# Power_Board_DRV8323.net
KiCad netlist of a schematic drawn in Altium Designer
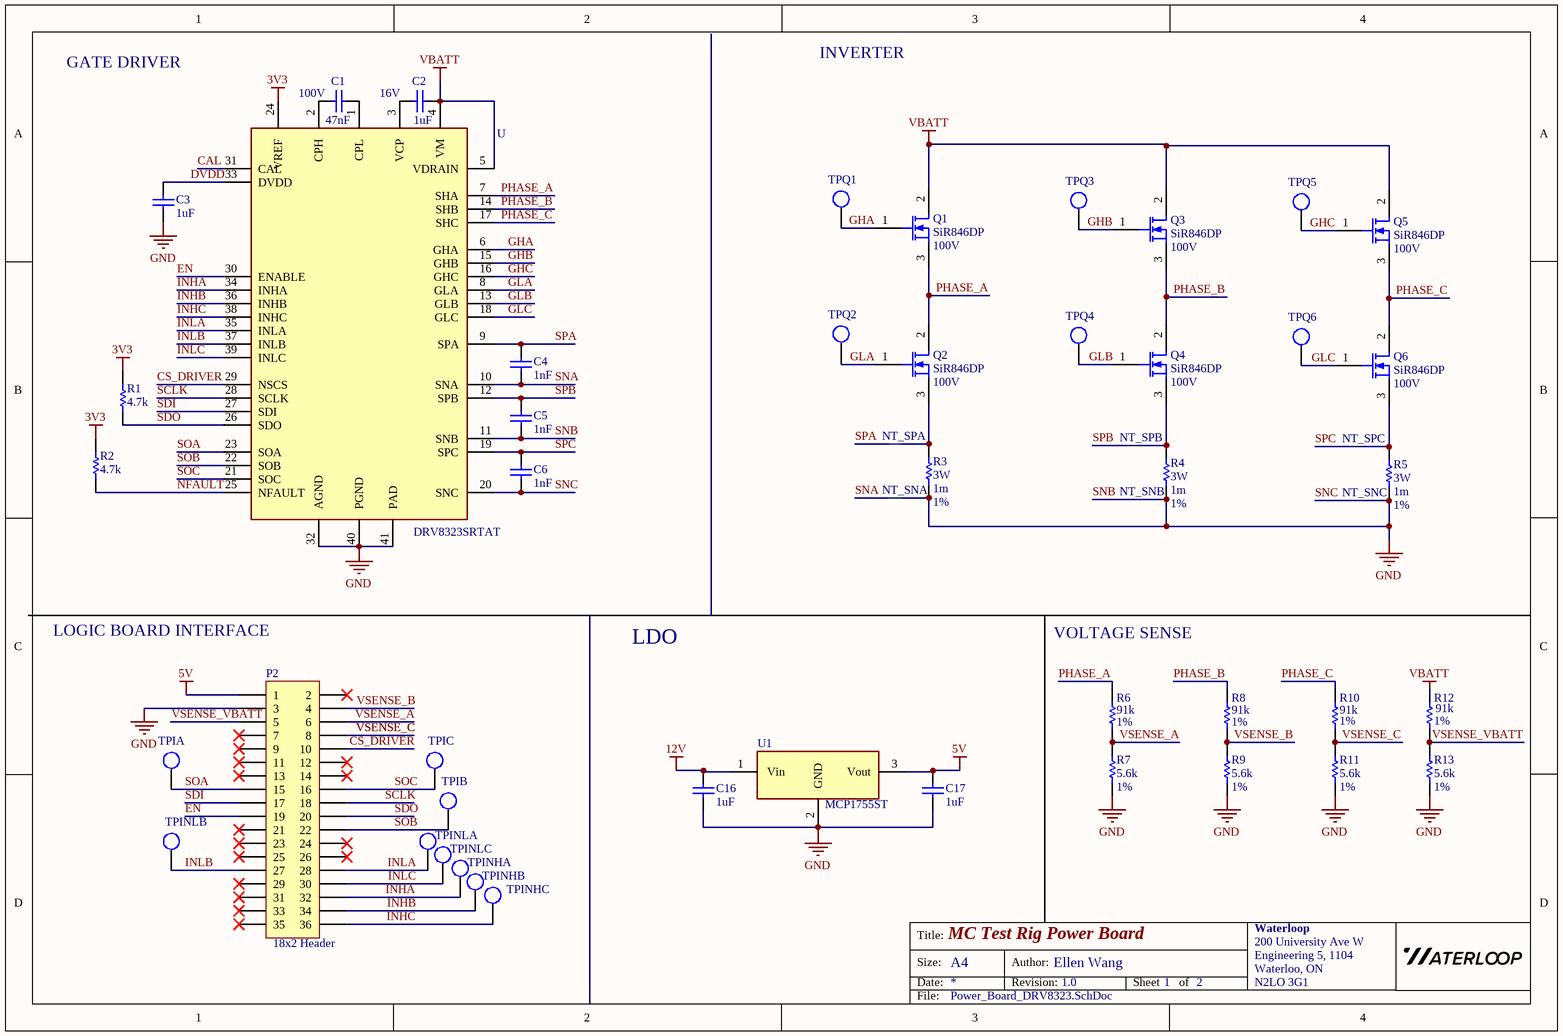
[diagram p0: Power_Board_DRV8323.SchDoc]

(export (version "E")
  (design (tool "Eeschema 10.0.6"))
  (components
    (comp (ref "C1")
      (value "47nF")
      (footprint "0805 - Capacitor")
      (description "Nonpolarized Capacitor")
      (fields
        (field (name "MANUFACTURER") "YAGEO")
        (field (name "RATING") "100V")
        (field (name "MANUFACTURER PART NUMBER") "CC0805KKX7R0BB473")
      )
      (libsource (lib "General") (part "Capacitor - Nonpolarized"))
    )
    (comp (ref "C2")
      (value "1uF")
      (footprint "0805 - Capacitor")
      (description "Nonpolarized Capacitor")
      (fields
        (field (name "MANUFACTURER") "YAGEO")
        (field (name "RATING") "16V")
        (field (name "MANUFACTURER PART NUMBER") "CC0805KKX7R7BB105")
      )
      (libsource (lib "General") (part "Capacitor - Nonpolarized"))
    )
    (comp (ref "C3")
      (value "1uF")
      (footprint "0805 - Capacitor")
      (description "Nonpolarized Capacitor")
      (fields
        (field (name "MANUFACTURER") "YAGEO")
        (field (name "MANUFACTURER PART NUMBER") "CC0805KKX7R7BB105")
      )
      (libsource (lib "General") (part "Capacitor - Nonpolarized"))
    )
    (comp (ref "C4")
      (value "1nF")
      (footprint "0805 - Capacitor")
      (description "Nonpolarized Capacitor")
      (fields
        (field (name "MANUFACTURER") "YAGEO")
        (field (name "MANUFACTURER PART NUMBER") "CC0805KRX7R0BB102")
      )
      (libsource (lib "General") (part "Capacitor - Nonpolarized"))
    )
    (comp (ref "C5")
      (value "1nF")
      (footprint "0805 - Capacitor")
      (description "Nonpolarized Capacitor")
      (fields
        (field (name "MANUFACTURER") "YAGEO")
        (field (name "MANUFACTURER PART NUMBER") "CC0805KRX7R0BB102")
      )
      (libsource (lib "General") (part "Capacitor - Nonpolarized"))
    )
    (comp (ref "C6")
      (value "1nF")
      (footprint "0805 - Capacitor")
      (description "Nonpolarized Capacitor")
      (fields
        (field (name "MANUFACTURER") "YAGEO")
        (field (name "MANUFACTURER PART NUMBER") "CC0805KRX7R0BB102")
      )
      (libsource (lib "General") (part "Capacitor - Nonpolarized"))
    )
    (comp (ref "C16")
      (value "1uF")
      (footprint "0805 - Capacitor")
      (description "Nonpolarized Capacitor")
      (fields (field (name "Comment") "Capacitor - Nonpolarized"))
      (libsource (lib "General") (part "Capacitor - Nonpolarized"))
    )
    (comp (ref "C17")
      (value "1uF")
      (footprint "0805 - Capacitor")
      (description "Nonpolarized Capacitor")
      (fields (field (name "Comment") "Capacitor - Nonpolarized"))
      (libsource (lib "General") (part "Capacitor - Nonpolarized"))
    )
    (comp (ref "NT_SNA") (value "NetTie") (footprint "Net Tie") (libsource (lib "General") (part "Net Tie")))
    (comp (ref "NT_SNB") (value "NetTie") (footprint "Net Tie") (libsource (lib "General") (part "Net Tie")))
    (comp (ref "NT_SNC") (value "NetTie") (footprint "Net Tie") (libsource (lib "General") (part "Net Tie")))
    (comp (ref "NT_SPA") (value "NetTie") (footprint "Net Tie") (libsource (lib "General") (part "Net Tie")))
    (comp (ref "NT_SPB") (value "NetTie") (footprint "Net Tie") (libsource (lib "General") (part "Net Tie")))
    (comp (ref "NT_SPC") (value "NetTie") (footprint "Net Tie") (libsource (lib "General") (part "Net Tie")))
    (comp (ref "P2")
      (value "Header 18X2")
      (footprint "HDR2X18")
      (description "Header, 18-Pin, Dual row")
      (fields (field (name "PUBLISHER") "Altium Limited"))
      (libsource (lib "Miscellaneous Connectors") (part "Header 18X2"))
    )
    (comp (ref "Q1")
      (value "MOSFET-N")
      (footprint "PowerPAK® SO-8")
      (description "N-Channel MOSFET")
      (fields (field (name "SUPPLIER PART NUMBER") "SiR846DP") (field (name "RATING") "100V"))
      (libsource (lib "General") (part "MOSFET-N"))
    )
    (comp (ref "Q2")
      (value "MOSFET-N")
      (footprint "PowerPAK® SO-8")
      (description "N-Channel MOSFET")
      (fields (field (name "SUPPLIER PART NUMBER") "SiR846DP") (field (name "RATING") "100V"))
      (libsource (lib "General") (part "MOSFET-N"))
    )
    (comp (ref "Q3")
      (value "MOSFET-N")
      (footprint "PowerPAK® SO-8")
      (description "N-Channel MOSFET")
      (fields (field (name "SUPPLIER PART NUMBER") "SiR846DP") (field (name "RATING") "100V"))
      (libsource (lib "General") (part "MOSFET-N"))
    )
    (comp (ref "Q4")
      (value "MOSFET-N")
      (footprint "PowerPAK® SO-8")
      (description "N-Channel MOSFET")
      (fields (field (name "SUPPLIER PART NUMBER") "SiR846DP") (field (name "RATING") "100V"))
      (libsource (lib "General") (part "MOSFET-N"))
    )
    (comp (ref "Q5")
      (value "MOSFET-N")
      (footprint "PowerPAK® SO-8")
      (description "N-Channel MOSFET")
      (fields (field (name "SUPPLIER PART NUMBER") "SiR846DP") (field (name "RATING") "100V"))
      (libsource (lib "General") (part "MOSFET-N"))
    )
    (comp (ref "Q6")
      (value "MOSFET-N")
      (footprint "PowerPAK® SO-8")
      (description "N-Channel MOSFET")
      (fields (field (name "SUPPLIER PART NUMBER") "SiR846DP") (field (name "RATING") "100V"))
      (libsource (lib "General") (part "MOSFET-N"))
    )
    (comp (ref "R1")
      (value "4.7k")
      (footprint "0603 - Resistor")
      (description "Resistor")
      (fields
        (field (name "MANUFACTURER PART NUMBER") "RC0603FR-074K7L")
        (field (name "MANUFACTURER") "YAGEO")
      )
      (libsource (lib "General") (part "Resistor"))
    )
    (comp (ref "R2")
      (value "4.7k")
      (footprint "0603 - Resistor")
      (description "Resistor")
      (fields
        (field (name "MANUFACTURER PART NUMBER") "RC0603FR-074K7L")
        (field (name "MANUFACTURER") "YAGEO")
      )
      (libsource (lib "General") (part "Resistor"))
    )
    (comp (ref "R3")
      (value "1m")
      (footprint "2512 - RESISTOR")
      (description "Resistor")
      (fields
        (field (name "RATING") "3W")
        (field (name "MANUFACTURER PART NUMBER") "CSR2512C0R001F")
        (field (name "MANUFACTURER") "Riedon")
        (field (name "TOLERANCE") "1%")
      )
      (libsource (lib "General") (part "Resistor"))
    )
    (comp (ref "R4")
      (value "1m")
      (footprint "2512 - RESISTOR")
      (description "Resistor")
      (fields
        (field (name "RATING") "3W")
        (field (name "MANUFACTURER PART NUMBER") "CSR2512C0R001F")
        (field (name "MANUFACTURER") "Riedon")
        (field (name "TOLERANCE") "1%")
      )
      (libsource (lib "General") (part "Resistor"))
    )
    (comp (ref "R5")
      (value "1m")
      (footprint "2512 - RESISTOR")
      (description "Resistor")
      (fields
        (field (name "RATING") "3W")
        (field (name "MANUFACTURER PART NUMBER") "CSR2512C0R001F")
        (field (name "MANUFACTURER") "Riedon")
        (field (name "TOLERANCE") "1%")
      )
      (libsource (lib "General") (part "Resistor"))
    )
    (comp (ref "R6")
      (value "91k")
      (footprint "0603 - Resistor")
      (description "Resistor")
      (fields
        (field (name "MANUFACTURER PART NUMBER") "RC0603FR-0791KL")
        (field (name "MANUFACTURER") "YAGEO")
        (field (name "TOLERANCE") "1%")
      )
      (libsource (lib "General") (part "Resistor"))
    )
    (comp (ref "R7")
      (value "5.6k")
      (footprint "0603 - Resistor")
      (description "Resistor")
      (fields
        (field (name "MANUFACTURER PART NUMBER") "RC0603FR-075K6L")
        (field (name "MANUFACTURER") "YAGEO")
        (field (name "TOLERANCE") "1%")
      )
      (libsource (lib "General") (part "Resistor"))
    )
    (comp (ref "R8")
      (value "91k")
      (footprint "0603 - Resistor")
      (description "Resistor")
      (fields
        (field (name "MANUFACTURER PART NUMBER") "RC0603FR-0791KL")
        (field (name "MANUFACTURER") "YAGEO")
        (field (name "TOLERANCE") "1%")
      )
      (libsource (lib "General") (part "Resistor"))
    )
    (comp (ref "R9")
      (value "5.6k")
      (footprint "0603 - Resistor")
      (description "Resistor")
      (fields
        (field (name "MANUFACTURER PART NUMBER") "RC0603FR-075K6L")
        (field (name "MANUFACTURER") "YAGEO")
        (field (name "TOLERANCE") "1%")
      )
      (libsource (lib "General") (part "Resistor"))
    )
    (comp (ref "R10")
      (value "91k")
      (footprint "0603 - Resistor")
      (description "Resistor")
      (fields
        (field (name "MANUFACTURER PART NUMBER") "RC0603FR-0791KL")
        (field (name "MANUFACTURER") "YAGEO")
        (field (name "TOLERANCE") "1%")
      )
      (libsource (lib "General") (part "Resistor"))
    )
    (comp (ref "R11")
      (value "5.6k")
      (footprint "0603 - Resistor")
      (description "Resistor")
      (fields
        (field (name "MANUFACTURER PART NUMBER") "RC0603FR-075K6L")
        (field (name "MANUFACTURER") "YAGEO")
        (field (name "TOLERANCE") "1%")
      )
      (libsource (lib "General") (part "Resistor"))
    )
    (comp (ref "R12")
      (value "91k")
      (footprint "0603 - Resistor")
      (description "Resistor")
      (fields
        (field (name "MANUFACTURER PART NUMBER") "RC0603FR-0791KL")
        (field (name "MANUFACTURER") "YAGEO")
        (field (name "TOLERANCE") "1%")
      )
      (libsource (lib "General") (part "Resistor"))
    )
    (comp (ref "R13")
      (value "5.6k")
      (footprint "0603 - Resistor")
      (description "Resistor")
      (fields
        (field (name "MANUFACTURER PART NUMBER") "RC0603FR-075K6L")
        (field (name "MANUFACTURER") "YAGEO")
        (field (name "TOLERANCE") "1%")
      )
      (libsource (lib "General") (part "Resistor"))
    )
    (comp (ref "TPIA")
      (value "Test Point")
      (footprint "Test Point")
      (libsource (lib "General") (part "Test Point"))
    )
    (comp (ref "TPIB")
      (value "Test Point")
      (footprint "Test Point")
      (libsource (lib "General") (part "Test Point"))
    )
    (comp (ref "TPIC")
      (value "Test Point")
      (footprint "Test Point")
      (libsource (lib "General") (part "Test Point"))
    )
    (comp (ref "TPINHA")
      (value "Test Point")
      (footprint "Test Point")
      (libsource (lib "General") (part "Test Point"))
    )
    (comp (ref "TPINHB")
      (value "Test Point")
      (footprint "Test Point")
      (libsource (lib "General") (part "Test Point"))
    )
    (comp (ref "TPINHC")
      (value "Test Point")
      (footprint "Test Point")
      (libsource (lib "General") (part "Test Point"))
    )
    (comp (ref "TPINLA")
      (value "Test Point")
      (footprint "Test Point")
      (libsource (lib "General") (part "Test Point"))
    )
    (comp (ref "TPINLB")
      (value "Test Point")
      (footprint "Test Point")
      (libsource (lib "General") (part "Test Point"))
    )
    (comp (ref "TPINLC")
      (value "Test Point")
      (footprint "Test Point")
      (libsource (lib "General") (part "Test Point"))
    )
    (comp (ref "TPQ1")
      (value "Test Point")
      (footprint "Test Point")
      (libsource (lib "General") (part "Test Point"))
    )
    (comp (ref "TPQ2")
      (value "Test Point")
      (footprint "Test Point")
      (libsource (lib "General") (part "Test Point"))
    )
    (comp (ref "TPQ3")
      (value "Test Point")
      (footprint "Test Point")
      (libsource (lib "General") (part "Test Point"))
    )
    (comp (ref "TPQ4")
      (value "Test Point")
      (footprint "Test Point")
      (libsource (lib "General") (part "Test Point"))
    )
    (comp (ref "TPQ5")
      (value "Test Point")
      (footprint "Test Point")
      (libsource (lib "General") (part "Test Point"))
    )
    (comp (ref "TPQ6")
      (value "Test Point")
      (footprint "Test Point")
      (libsource (lib "General") (part "Test Point"))
    )
    (comp (ref "U")
      (value "DRV8323SRTAT")
      (footprint "DRV8323SRTAT")
      (description "Multiphase Motor Driver Power MOSFET SPI")
      (fields (field (name "MANUFACTURER") "Texas Instruments"))
      (libsource (lib "MC") (part "DRV8323SRTAT"))
    )
    (comp (ref "U1")
      (value "MCP1755ST")
      (footprint "MCP1755ST")
      (libsource (lib "GeneralComponents") (part "MCP1755ST"))
    )
  )
  (nets
    (net (code "1") (name "/CAL") (class "Default")
      (node (ref "U") (pin "31") (pinfunction "CAL_31") (pintype "passive"))
    )
    (net (code "2") (name "/CS_DRIVER") (class "Default")
      (node (ref "P2") (pin "10") (pinfunction "10_10") (pintype "passive"))
      (node (ref "U") (pin "29") (pinfunction "NSCS_29") (pintype "passive"))
    )
    (net (code "3") (name "/DVDD") (class "Default")
      (node (ref "C3") (pin "2") (pinfunction "2_2") (pintype "passive"))
      (node (ref "U") (pin "33") (pinfunction "DVDD_33") (pintype "power_in"))
    )
    (net (code "4") (name "/EN") (class "Default")
      (node (ref "P2") (pin "19") (pinfunction "19_19") (pintype "passive"))
      (node (ref "U") (pin "30") (pinfunction "ENABLE_30") (pintype "passive"))
    )
    (net (code "5") (name "/GHA") (class "Default")
      (node (ref "Q1") (pin "1") (pinfunction "G_1") (pintype "passive"))
      (node (ref "TPQ1") (pin "1") (pinfunction "0_1") (pintype "passive"))
      (node (ref "U") (pin "6") (pinfunction "GHA_6") (pintype "passive"))
    )
    (net (code "6") (name "/GHB") (class "Default")
      (node (ref "Q3") (pin "1") (pinfunction "G_1") (pintype "passive"))
      (node (ref "TPQ3") (pin "1") (pinfunction "0_1") (pintype "passive"))
      (node (ref "U") (pin "15") (pinfunction "GHB_15") (pintype "passive"))
    )
    (net (code "7") (name "/GHC") (class "Default")
      (node (ref "Q5") (pin "1") (pinfunction "G_1") (pintype "passive"))
      (node (ref "TPQ5") (pin "1") (pinfunction "0_1") (pintype "passive"))
      (node (ref "U") (pin "16") (pinfunction "GHC_16") (pintype "passive"))
    )
    (net (code "8") (name "/GLA") (class "Default")
      (node (ref "Q2") (pin "1") (pinfunction "G_1") (pintype "passive"))
      (node (ref "TPQ2") (pin "1") (pinfunction "0_1") (pintype "passive"))
      (node (ref "U") (pin "8") (pinfunction "GLA_8") (pintype "passive"))
    )
    (net (code "9") (name "/GLB") (class "Default")
      (node (ref "Q4") (pin "1") (pinfunction "G_1") (pintype "passive"))
      (node (ref "TPQ4") (pin "1") (pinfunction "0_1") (pintype "passive"))
      (node (ref "U") (pin "13") (pinfunction "GLB_13") (pintype "passive"))
    )
    (net (code "10") (name "/GLC") (class "Default")
      (node (ref "Q6") (pin "1") (pinfunction "G_1") (pintype "passive"))
      (node (ref "TPQ6") (pin "1") (pinfunction "0_1") (pintype "passive"))
      (node (ref "U") (pin "18") (pinfunction "GLC_18") (pintype "passive"))
    )
    (net (code "11") (name "/INHA") (class "Default")
      (node (ref "P2") (pin "32") (pinfunction "32_32") (pintype "passive"))
      (node (ref "TPINHA") (pin "1") (pinfunction "0_1") (pintype "passive"))
      (node (ref "U") (pin "34") (pinfunction "INHA_34") (pintype "passive"))
    )
    (net (code "12") (name "/INHB") (class "Default")
      (node (ref "P2") (pin "34") (pinfunction "34_34") (pintype "passive"))
      (node (ref "TPINHB") (pin "1") (pinfunction "0_1") (pintype "passive"))
      (node (ref "U") (pin "36") (pinfunction "INHB_36") (pintype "passive"))
    )
    (net (code "13") (name "/INHC") (class "Default")
      (node (ref "P2") (pin "36") (pinfunction "36_36") (pintype "passive"))
      (node (ref "TPINHC") (pin "1") (pinfunction "0_1") (pintype "passive"))
      (node (ref "U") (pin "38") (pinfunction "INHC_38") (pintype "passive"))
    )
    (net (code "14") (name "/INLA") (class "Default")
      (node (ref "P2") (pin "28") (pinfunction "28_28") (pintype "passive"))
      (node (ref "TPINLA") (pin "1") (pinfunction "0_1") (pintype "passive"))
      (node (ref "U") (pin "35") (pinfunction "INLA_35") (pintype "passive"))
    )
    (net (code "15") (name "/INLB") (class "Default")
      (node (ref "P2") (pin "27") (pinfunction "27_27") (pintype "passive"))
      (node (ref "TPINLB") (pin "1") (pinfunction "0_1") (pintype "passive"))
      (node (ref "U") (pin "37") (pinfunction "INLB_37") (pintype "passive"))
    )
    (net (code "16") (name "/INLC") (class "Default")
      (node (ref "P2") (pin "30") (pinfunction "30_30") (pintype "passive"))
      (node (ref "TPINLC") (pin "1") (pinfunction "0_1") (pintype "passive"))
      (node (ref "U") (pin "39") (pinfunction "INLC_39") (pintype "passive"))
    )
    (net (code "17") (name "/NFAULT") (class "Default")
      (node (ref "R2") (pin "1") (pinfunction "1_1") (pintype "passive"))
      (node (ref "U") (pin "25") (pinfunction "NFAULT_25") (pintype "passive"))
    )
    (net (code "18") (name "/PHASE_A") (class "Default")
      (node (ref "Q1") (pin "3") (pinfunction "S_3") (pintype "passive"))
      (node (ref "Q2") (pin "2") (pinfunction "D_2") (pintype "passive"))
      (node (ref "R6") (pin "1") (pinfunction "1_1") (pintype "passive"))
      (node (ref "U") (pin "7") (pinfunction "SHA_7") (pintype "passive"))
    )
    (net (code "19") (name "/PHASE_B") (class "Default")
      (node (ref "Q3") (pin "3") (pinfunction "S_3") (pintype "passive"))
      (node (ref "Q4") (pin "2") (pinfunction "D_2") (pintype "passive"))
      (node (ref "R8") (pin "1") (pinfunction "1_1") (pintype "passive"))
      (node (ref "U") (pin "14") (pinfunction "SHB_14") (pintype "passive"))
    )
    (net (code "20") (name "/PHASE_C") (class "Default")
      (node (ref "Q5") (pin "3") (pinfunction "S_3") (pintype "passive"))
      (node (ref "Q6") (pin "2") (pinfunction "D_2") (pintype "passive"))
      (node (ref "R10") (pin "1") (pinfunction "1_1") (pintype "passive"))
      (node (ref "U") (pin "17") (pinfunction "SHC_17") (pintype "passive"))
    )
    (net (code "21") (name "/SCLK") (class "Default")
      (node (ref "P2") (pin "18") (pinfunction "18_18") (pintype "passive"))
      (node (ref "U") (pin "28") (pinfunction "SCLK_28") (pintype "passive"))
    )
    (net (code "22") (name "/SDI") (class "Default")
      (node (ref "P2") (pin "17") (pinfunction "17_17") (pintype "passive"))
      (node (ref "U") (pin "27") (pinfunction "SDI_27") (pintype "passive"))
    )
    (net (code "23") (name "/SDO") (class "Default")
      (node (ref "P2") (pin "20") (pinfunction "20_20") (pintype "passive"))
      (node (ref "R1") (pin "1") (pinfunction "1_1") (pintype "passive"))
      (node (ref "U") (pin "26") (pinfunction "SDO_26") (pintype "passive"))
    )
    (net (code "24") (name "/SNA") (class "Default")
      (node (ref "C4") (pin "1") (pinfunction "1_1") (pintype "passive"))
      (node (ref "NT_SNA") (pin "1") (pinfunction "1_1") (pintype "passive"))
      (node (ref "U") (pin "10") (pinfunction "SNA_10") (pintype "passive"))
    )
    (net (code "25") (name "/SNB") (class "Default")
      (node (ref "C5") (pin "1") (pinfunction "1_1") (pintype "passive"))
      (node (ref "NT_SNB") (pin "1") (pinfunction "1_1") (pintype "passive"))
      (node (ref "U") (pin "11") (pinfunction "SNB_11") (pintype "passive"))
    )
    (net (code "26") (name "/SNC") (class "Default")
      (node (ref "C6") (pin "1") (pinfunction "1_1") (pintype "passive"))
      (node (ref "NT_SNC") (pin "1") (pinfunction "1_1") (pintype "passive"))
      (node (ref "U") (pin "20") (pinfunction "SNC_20") (pintype "passive"))
    )
    (net (code "27") (name "/SOA") (class "Default")
      (node (ref "P2") (pin "15") (pinfunction "15_15") (pintype "passive"))
      (node (ref "TPIA") (pin "1") (pinfunction "0_1") (pintype "passive"))
      (node (ref "U") (pin "23") (pinfunction "SOA_23") (pintype "passive"))
    )
    (net (code "28") (name "/SOB") (class "Default")
      (node (ref "P2") (pin "22") (pinfunction "22_22") (pintype "passive"))
      (node (ref "TPIB") (pin "1") (pinfunction "0_1") (pintype "passive"))
      (node (ref "U") (pin "22") (pinfunction "SOB_22") (pintype "passive"))
    )
    (net (code "29") (name "/SOC") (class "Default")
      (node (ref "P2") (pin "16") (pinfunction "16_16") (pintype "passive"))
      (node (ref "TPIC") (pin "1") (pinfunction "0_1") (pintype "passive"))
      (node (ref "U") (pin "21") (pinfunction "SOC_21") (pintype "passive"))
    )
    (net (code "30") (name "/SPA") (class "Default")
      (node (ref "C4") (pin "2") (pinfunction "2_2") (pintype "passive"))
      (node (ref "NT_SPA") (pin "1") (pinfunction "1_1") (pintype "passive"))
      (node (ref "U") (pin "9") (pinfunction "SPA_9") (pintype "passive"))
    )
    (net (code "31") (name "/SPB") (class "Default")
      (node (ref "C5") (pin "2") (pinfunction "2_2") (pintype "passive"))
      (node (ref "NT_SPB") (pin "1") (pinfunction "1_1") (pintype "passive"))
      (node (ref "U") (pin "12") (pinfunction "SPB_12") (pintype "passive"))
    )
    (net (code "32") (name "/SPC") (class "Default")
      (node (ref "C6") (pin "2") (pinfunction "2_2") (pintype "passive"))
      (node (ref "NT_SPC") (pin "1") (pinfunction "1_1") (pintype "passive"))
      (node (ref "U") (pin "19") (pinfunction "SPC_19") (pintype "passive"))
    )
    (net (code "33") (name "/VSENSE_A") (class "Default")
      (node (ref "P2") (pin "6") (pinfunction "6_6") (pintype "passive"))
      (node (ref "R6") (pin "2") (pinfunction "2_2") (pintype "passive"))
      (node (ref "R7") (pin "1") (pinfunction "1_1") (pintype "passive"))
    )
    (net (code "34") (name "/VSENSE_B") (class "Default")
      (node (ref "P2") (pin "4") (pinfunction "4_4") (pintype "passive"))
      (node (ref "R8") (pin "2") (pinfunction "2_2") (pintype "passive"))
      (node (ref "R9") (pin "1") (pinfunction "1_1") (pintype "passive"))
    )
    (net (code "35") (name "/VSENSE_C") (class "Default")
      (node (ref "P2") (pin "8") (pinfunction "8_8") (pintype "passive"))
      (node (ref "R10") (pin "2") (pinfunction "2_2") (pintype "passive"))
      (node (ref "R11") (pin "1") (pinfunction "1_1") (pintype "passive"))
    )
    (net (code "36") (name "/VSENSE_VBATT") (class "Default")
      (node (ref "P2") (pin "5") (pinfunction "5_5") (pintype "passive"))
      (node (ref "R12") (pin "2") (pinfunction "2_2") (pintype "passive"))
      (node (ref "R13") (pin "1") (pinfunction "1_1") (pintype "passive"))
    )
    (net (code "37") (name "3V3") (class "Default")
      (node (ref "R1") (pin "2") (pinfunction "2_2") (pintype "passive"))
      (node (ref "R2") (pin "2") (pinfunction "2_2") (pintype "passive"))
      (node (ref "U") (pin "24") (pinfunction "VREF_24") (pintype "power_in"))
    )
    (net (code "38") (name "5V") (class "Default")
      (node (ref "C17") (pin "2") (pinfunction "2_2") (pintype "passive"))
      (node (ref "P2") (pin "1") (pinfunction "1_1") (pintype "passive"))
      (node (ref "U1") (pin "3") (pinfunction "Vout_3") (pintype "passive"))
    )
    (net (code "39") (name "12V") (class "Default")
      (node (ref "C16") (pin "2") (pinfunction "2_2") (pintype "passive"))
      (node (ref "U1") (pin "1") (pinfunction "Vin_1") (pintype "passive"))
    )
    (net (code "40") (name "GND") (class "Default")
      (node (ref "C16") (pin "1") (pinfunction "1_1") (pintype "passive"))
      (node (ref "C17") (pin "1") (pinfunction "1_1") (pintype "passive"))
      (node (ref "C3") (pin "1") (pinfunction "1_1") (pintype "passive"))
      (node (ref "NT_SNA") (pin "2") (pinfunction "2_2") (pintype "passive"))
      (node (ref "NT_SNB") (pin "2") (pinfunction "2_2") (pintype "passive"))
      (node (ref "NT_SNC") (pin "2") (pinfunction "2_2") (pintype "passive"))
      (node (ref "P2") (pin "3") (pinfunction "3_3") (pintype "passive"))
      (node (ref "R11") (pin "2") (pinfunction "2_2") (pintype "passive"))
      (node (ref "R13") (pin "2") (pinfunction "2_2") (pintype "passive"))
      (node (ref "R3") (pin "1") (pinfunction "1_1") (pintype "passive"))
      (node (ref "R4") (pin "1") (pinfunction "1_1") (pintype "passive"))
      (node (ref "R5") (pin "1") (pinfunction "1_1") (pintype "passive"))
      (node (ref "R7") (pin "2") (pinfunction "2_2") (pintype "passive"))
      (node (ref "R9") (pin "2") (pinfunction "2_2") (pintype "passive"))
      (node (ref "U1") (pin "2") (pinfunction "GND_2") (pintype "passive"))
    )
    (net (code "41") (name "Net-(Q2-S)") (class "Default")
      (node (ref "NT_SPA") (pin "2") (pinfunction "2_2") (pintype "passive"))
      (node (ref "Q2") (pin "3") (pinfunction "S_3") (pintype "passive"))
      (node (ref "R3") (pin "2") (pinfunction "2_2") (pintype "passive"))
    )
    (net (code "42") (name "Net-(Q4-S)") (class "Default")
      (node (ref "NT_SPB") (pin "2") (pinfunction "2_2") (pintype "passive"))
      (node (ref "Q4") (pin "3") (pinfunction "S_3") (pintype "passive"))
      (node (ref "R4") (pin "2") (pinfunction "2_2") (pintype "passive"))
    )
    (net (code "43") (name "Net-(Q6-S)") (class "Default")
      (node (ref "NT_SPC") (pin "2") (pinfunction "2_2") (pintype "passive"))
      (node (ref "Q6") (pin "3") (pinfunction "S_3") (pintype "passive"))
      (node (ref "R5") (pin "2") (pinfunction "2_2") (pintype "passive"))
    )
    (net (code "44") (name "Net-(U-AGND)") (class "Default")
      (node (ref "U") (pin "32") (pinfunction "AGND_32") (pintype "power_in"))
      (node (ref "U") (pin "40") (pinfunction "PGND_40") (pintype "power_in"))
      (node (ref "U") (pin "41") (pinfunction "PAD_41") (pintype "power_in"))
    )
    (net (code "45") (name "Net-(U-CPH)") (class "Default")
      (node (ref "C1") (pin "1") (pinfunction "1_1") (pintype "passive"))
      (node (ref "U") (pin "2") (pinfunction "CPH_2") (pintype "power_in"))
    )
    (net (code "46") (name "Net-(U-CPL)") (class "Default")
      (node (ref "C1") (pin "2") (pinfunction "2_2") (pintype "passive"))
      (node (ref "U") (pin "1") (pinfunction "CPL_1") (pintype "power_in"))
    )
    (net (code "47") (name "Net-(U-VCP)") (class "Default")
      (node (ref "C2") (pin "1") (pinfunction "1_1") (pintype "passive"))
      (node (ref "U") (pin "3") (pinfunction "VCP_3") (pintype "power_in"))
    )
    (net (code "48") (name "VBATT") (class "Default")
      (node (ref "C2") (pin "2") (pinfunction "2_2") (pintype "passive"))
      (node (ref "Q1") (pin "2") (pinfunction "D_2") (pintype "passive"))
      (node (ref "Q3") (pin "2") (pinfunction "D_2") (pintype "passive"))
      (node (ref "Q5") (pin "2") (pinfunction "D_2") (pintype "passive"))
      (node (ref "R12") (pin "1") (pinfunction "1_1") (pintype "passive"))
      (node (ref "U") (pin "4") (pinfunction "VM_4") (pintype "power_in"))
      (node (ref "U") (pin "5") (pinfunction "VDRAIN_5") (pintype "passive"))
    )
    (net (code "49") (name "unconnected-(P2-Pad2)") (class "Default")
      (node (ref "P2") (pin "2") (pinfunction "2_2") (pintype "passive+no_connect"))
    )
    (net (code "50") (name "unconnected-(P2-Pad7)") (class "Default")
      (node (ref "P2") (pin "7") (pinfunction "7_7") (pintype "passive+no_connect"))
    )
    (net (code "51") (name "unconnected-(P2-Pad9)") (class "Default")
      (node (ref "P2") (pin "9") (pinfunction "9_9") (pintype "passive+no_connect"))
    )
    (net (code "52") (name "unconnected-(P2-Pad11)") (class "Default")
      (node (ref "P2") (pin "11") (pinfunction "11_11") (pintype "passive+no_connect"))
    )
    (net (code "53") (name "unconnected-(P2-Pad12)") (class "Default")
      (node (ref "P2") (pin "12") (pinfunction "12_12") (pintype "passive+no_connect"))
    )
    (net (code "54") (name "unconnected-(P2-Pad13)") (class "Default")
      (node (ref "P2") (pin "13") (pinfunction "13_13") (pintype "passive+no_connect"))
    )
    (net (code "55") (name "unconnected-(P2-Pad14)") (class "Default")
      (node (ref "P2") (pin "14") (pinfunction "14_14") (pintype "passive+no_connect"))
    )
    (net (code "56") (name "unconnected-(P2-Pad21)") (class "Default")
      (node (ref "P2") (pin "21") (pinfunction "21_21") (pintype "passive+no_connect"))
    )
    (net (code "57") (name "unconnected-(P2-Pad23)") (class "Default")
      (node (ref "P2") (pin "23") (pinfunction "23_23") (pintype "passive+no_connect"))
    )
    (net (code "58") (name "unconnected-(P2-Pad24)") (class "Default")
      (node (ref "P2") (pin "24") (pinfunction "24_24") (pintype "passive+no_connect"))
    )
    (net (code "59") (name "unconnected-(P2-Pad25)") (class "Default")
      (node (ref "P2") (pin "25") (pinfunction "25_25") (pintype "passive+no_connect"))
    )
    (net (code "60") (name "unconnected-(P2-Pad26)") (class "Default")
      (node (ref "P2") (pin "26") (pinfunction "26_26") (pintype "passive+no_connect"))
    )
    (net (code "61") (name "unconnected-(P2-Pad29)") (class "Default")
      (node (ref "P2") (pin "29") (pinfunction "29_29") (pintype "passive+no_connect"))
    )
    (net (code "62") (name "unconnected-(P2-Pad31)") (class "Default")
      (node (ref "P2") (pin "31") (pinfunction "31_31") (pintype "passive+no_connect"))
    )
    (net (code "63") (name "unconnected-(P2-Pad33)") (class "Default")
      (node (ref "P2") (pin "33") (pinfunction "33_33") (pintype "passive+no_connect"))
    )
    (net (code "64") (name "unconnected-(P2-Pad35)") (class "Default")
      (node (ref "P2") (pin "35") (pinfunction "35_35") (pintype "passive+no_connect"))
    )
  )
)
